# BreakoutPcb.net
KiCad netlist of a schematic drawn in Altium Designer
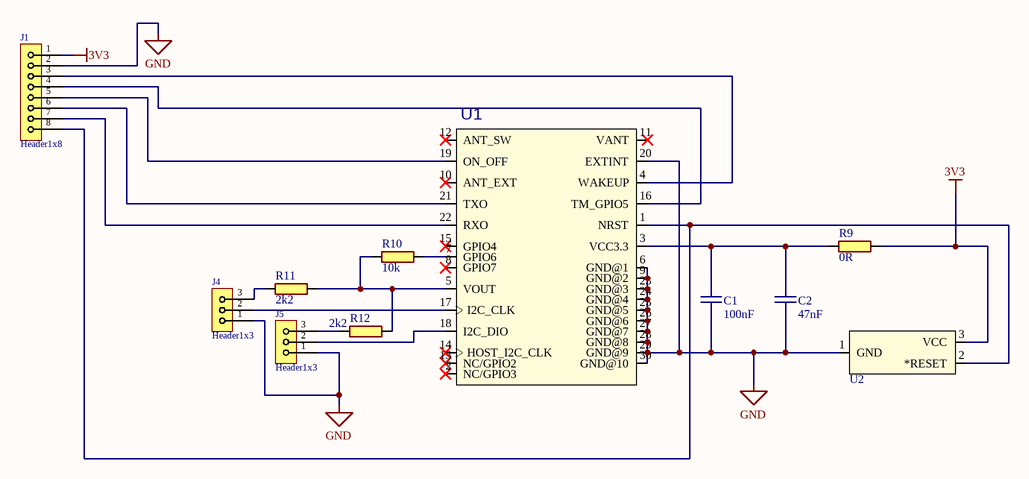
[diagram p0: BreakoutPcb.SchDoc]

(export (version "E")
  (design (tool "Eeschema 10.0.6"))
  (components
    (comp (ref "C1")
      (value "100nF")
      (footprint "CAPC0603(1608)55_N")
      (description "X7R 50V 5%")
      (libsource (lib "OVLib") (part "CAP"))
    )
    (comp (ref "C2")
      (value "47nF")
      (footprint "CAPC0805(2012)100_N")
      (description "X7R")
      (libsource (lib "OVLib") (part "CAP"))
    )
    (comp (ref "J1")
      (value "Header1x8")
      (footprint "HDRV8W64P254_1X8_2032X254X900B")
      (libsource (lib "OVLib") (part "Header1x8"))
    )
    (comp (ref "J4")
      (value "Header1x3")
      (footprint "HDRV3W64P254_1X3_762X254X900B")
      (libsource (lib "OVLib") (part "Header1x3"))
    )
    (comp (ref "J5")
      (value "Header1x3")
      (footprint "HDRV3W64P254_1X3_762X254X900B")
      (libsource (lib "OVLib") (part "Header1x3"))
    )
    (comp (ref "R9")
      (value "0R")
      (footprint "RESC0603(1608)_N")
      (description "0.1W 1% Thick film resistor")
      (libsource (lib "OVLib") (part "Resistor2"))
    )
    (comp (ref "R10")
      (value "10k")
      (footprint "RESC0603(1608)_N")
      (description "0.1W 1% Thick film resistor")
      (libsource (lib "OVLib") (part "Resistor2"))
    )
    (comp (ref "R11")
      (value "2k2")
      (footprint "RESC0603(1608)_N")
      (description "0.1W 1% Thick film resistor")
      (libsource (lib "OVLib") (part "Resistor2"))
    )
    (comp (ref "R12")
      (value "2k2")
      (footprint "RESC0603(1608)_N")
      (description "0.1W 1% Thick film resistor")
      (libsource (lib "OVLib") (part "Resistor2"))
    )
    (comp (ref "U1")
      (value "A2235-H")
      (footprint "XCVR_A2235-H")
      (description "Gps Module, Mini Outline w/ Ant")
      (fields (field (name "MF") "Maestro Wireless"))
      (libsource (lib "A2235-H") (part "A2235-H"))
    )
    (comp (ref "U2")
      (value "MAX809SEXR-T")
      (footprint "21-0075D")
      (description "PMIC - system monitor Maxim Integrated MAX809SEXR+T Reset/power-on reset SC 70 3")
      (fields (field (name "MP") "MAX809SEXR+T") (field (name "MF") "Maxim Integrated"))
      (libsource (lib "MAX809SEXR-T") (part "MAX809SEXR-T"))
    )
  )
  (nets
    (net (code "1") (name "3V3") (class "Default")
      (node (ref "J1") (pin "1") (pinfunction "1_1") (pintype "passive"))
      (node (ref "R9") (pin "2") (pinfunction "2_2") (pintype "passive"))
      (node (ref "U2") (pin "3") (pinfunction "VCC_3") (pintype "power_in"))
    )
    (net (code "2") (name "GND") (class "Default")
      (node (ref "C1") (pin "1") (pinfunction "1_1") (pintype "passive"))
      (node (ref "C2") (pin "1") (pinfunction "1_1") (pintype "passive"))
      (node (ref "J1") (pin "2") (pinfunction "2_2") (pintype "passive"))
      (node (ref "J4") (pin "1") (pinfunction "1_1") (pintype "passive"))
      (node (ref "J5") (pin "1") (pinfunction "1_1") (pintype "passive"))
      (node (ref "U1") (pin "20") (pinfunction "EXTINT_20") (pintype "input"))
      (node (ref "U1") (pin "23") (pinfunction "GND@3_23") (pintype "power_in"))
      (node (ref "U1") (pin "24") (pinfunction "GND@4_24") (pintype "power_in"))
      (node (ref "U1") (pin "25") (pinfunction "GND@5_25") (pintype "power_in"))
      (node (ref "U1") (pin "26") (pinfunction "GND@6_26") (pintype "power_in"))
      (node (ref "U1") (pin "27") (pinfunction "GND@7_27") (pintype "power_in"))
      (node (ref "U1") (pin "28") (pinfunction "GND@8_28") (pintype "power_in"))
      (node (ref "U1") (pin "29") (pinfunction "GND@9_29") (pintype "power_in"))
      (node (ref "U1") (pin "30") (pinfunction "GND@10_30") (pintype "power_in"))
      (node (ref "U1") (pin "6") (pinfunction "GND@1_6") (pintype "power_in"))
      (node (ref "U1") (pin "9") (pinfunction "GND@2_9") (pintype "power_in"))
      (node (ref "U2") (pin "1") (pinfunction "GND_1") (pintype "power_in"))
    )
    (net (code "3") (name "Net-(J4-Pad3)") (class "Default")
      (node (ref "J4") (pin "3") (pinfunction "3_3") (pintype "passive"))
      (node (ref "R11") (pin "1") (pinfunction "1_1") (pintype "passive"))
    )
    (net (code "4") (name "Net-(J5-Pad3)") (class "Default")
      (node (ref "J5") (pin "3") (pinfunction "3_3") (pintype "passive"))
      (node (ref "R12") (pin "1") (pinfunction "1_1") (pintype "passive"))
    )
    (net (code "5") (name "Net-(U1-GPIO6)") (class "Default")
      (node (ref "R10") (pin "2") (pinfunction "2_2") (pintype "passive"))
      (node (ref "U1") (pin "7") (pinfunction "GPIO6_7") (pintype "input"))
    )
    (net (code "6") (name "Net-(U1-I2C_CLK)") (class "Default")
      (node (ref "J4") (pin "2") (pinfunction "2_2") (pintype "passive"))
      (node (ref "U1") (pin "17") (pinfunction "I2C_CLK_17") (pintype "bidirectional"))
    )
    (net (code "7") (name "Net-(U1-I2C_DIO)") (class "Default")
      (node (ref "J5") (pin "2") (pinfunction "2_2") (pintype "passive"))
      (node (ref "U1") (pin "18") (pinfunction "I2C_DIO_18") (pintype "bidirectional"))
    )
    (net (code "8") (name "Net-(U1-NRST)") (class "Default")
      (node (ref "J1") (pin "8") (pinfunction "8_8") (pintype "passive"))
      (node (ref "U1") (pin "1") (pinfunction "NRST_1") (pintype "input"))
      (node (ref "U2") (pin "2") (pinfunction "*RESET_2") (pintype "output"))
    )
    (net (code "9") (name "Net-(U1-ON_OFF)") (class "Default")
      (node (ref "J1") (pin "5") (pinfunction "5_5") (pintype "passive"))
      (node (ref "U1") (pin "19") (pinfunction "ON_OFF_19") (pintype "input"))
    )
    (net (code "10") (name "Net-(U1-RXO)") (class "Default")
      (node (ref "J1") (pin "7") (pinfunction "7_7") (pintype "passive"))
      (node (ref "U1") (pin "22") (pinfunction "RXO_22") (pintype "input"))
    )
    (net (code "11") (name "Net-(U1-TM_GPIO5)") (class "Default")
      (node (ref "J1") (pin "4") (pinfunction "4_4") (pintype "passive"))
      (node (ref "U1") (pin "16") (pinfunction "TM_GPIO5_16") (pintype "output"))
    )
    (net (code "12") (name "Net-(U1-TXO)") (class "Default")
      (node (ref "J1") (pin "6") (pinfunction "6_6") (pintype "passive"))
      (node (ref "U1") (pin "21") (pinfunction "TXO_21") (pintype "output"))
    )
    (net (code "13") (name "Net-(U1-VCC3.3)") (class "Default")
      (node (ref "C1") (pin "2") (pinfunction "2_2") (pintype "passive"))
      (node (ref "C2") (pin "2") (pinfunction "2_2") (pintype "passive"))
      (node (ref "R9") (pin "1") (pinfunction "1_1") (pintype "passive"))
      (node (ref "U1") (pin "3") (pinfunction "VCC3.3_3") (pintype "power_in"))
    )
    (net (code "14") (name "Net-(U1-VOUT)") (class "Default")
      (node (ref "R10") (pin "1") (pinfunction "1_1") (pintype "passive"))
      (node (ref "R11") (pin "2") (pinfunction "2_2") (pintype "passive"))
      (node (ref "R12") (pin "2") (pinfunction "2_2") (pintype "passive"))
      (node (ref "U1") (pin "5") (pinfunction "VOUT_5") (pintype "output"))
    )
    (net (code "15") (name "Net-(U1-WAKEUP)") (class "Default")
      (node (ref "J1") (pin "3") (pinfunction "3_3") (pintype "passive"))
      (node (ref "U1") (pin "4") (pinfunction "WAKEUP_4") (pintype "output"))
    )
    (net (code "16") (name "unconnected-(U1-ANT_EXT-Pad10)") (class "Default")
      (node (ref "U1") (pin "10") (pinfunction "ANT_EXT_10") (pintype "input+no_connect"))
    )
    (net (code "17") (name "unconnected-(U1-ANT_SW-Pad12)") (class "Default")
      (node (ref "U1") (pin "12") (pinfunction "ANT_SW_12") (pintype "input+no_connect"))
    )
    (net (code "18") (name "unconnected-(U1-GPIO4-Pad15)") (class "Default")
      (node (ref "U1") (pin "15") (pinfunction "GPIO4_15") (pintype "input+no_connect"))
    )
    (net (code "19") (name "unconnected-(U1-GPIO7-Pad8)") (class "Default")
      (node (ref "U1") (pin "8") (pinfunction "GPIO7_8") (pintype "input+no_connect"))
    )
    (net (code "20") (name "unconnected-(U1-HOST_I2C_CLK-Pad14)") (class "Default")
      (node (ref "U1") (pin "14") (pinfunction "HOST_I2C_CLK_14") (pintype "bidirectional+no_connect"))
    )
    (net (code "21") (name "unconnected-(U1-NC{slash}GPIO2-Pad13)") (class "Default")
      (node (ref "U1") (pin "13") (pinfunction "NC/GPIO2_13") (pintype "bidirectional+no_connect"))
    )
    (net (code "22") (name "unconnected-(U1-NC{slash}GPIO3-Pad2)") (class "Default")
      (node (ref "U1") (pin "2") (pinfunction "NC/GPIO3_2") (pintype "bidirectional+no_connect"))
    )
    (net (code "23") (name "unconnected-(U1-VANT-Pad11)") (class "Default")
      (node (ref "U1") (pin "11") (pinfunction "VANT_11") (pintype "power_in+no_connect"))
    )
  )
)
